# JTAG.net
KiCad netlist of a schematic drawn in Altium Designer
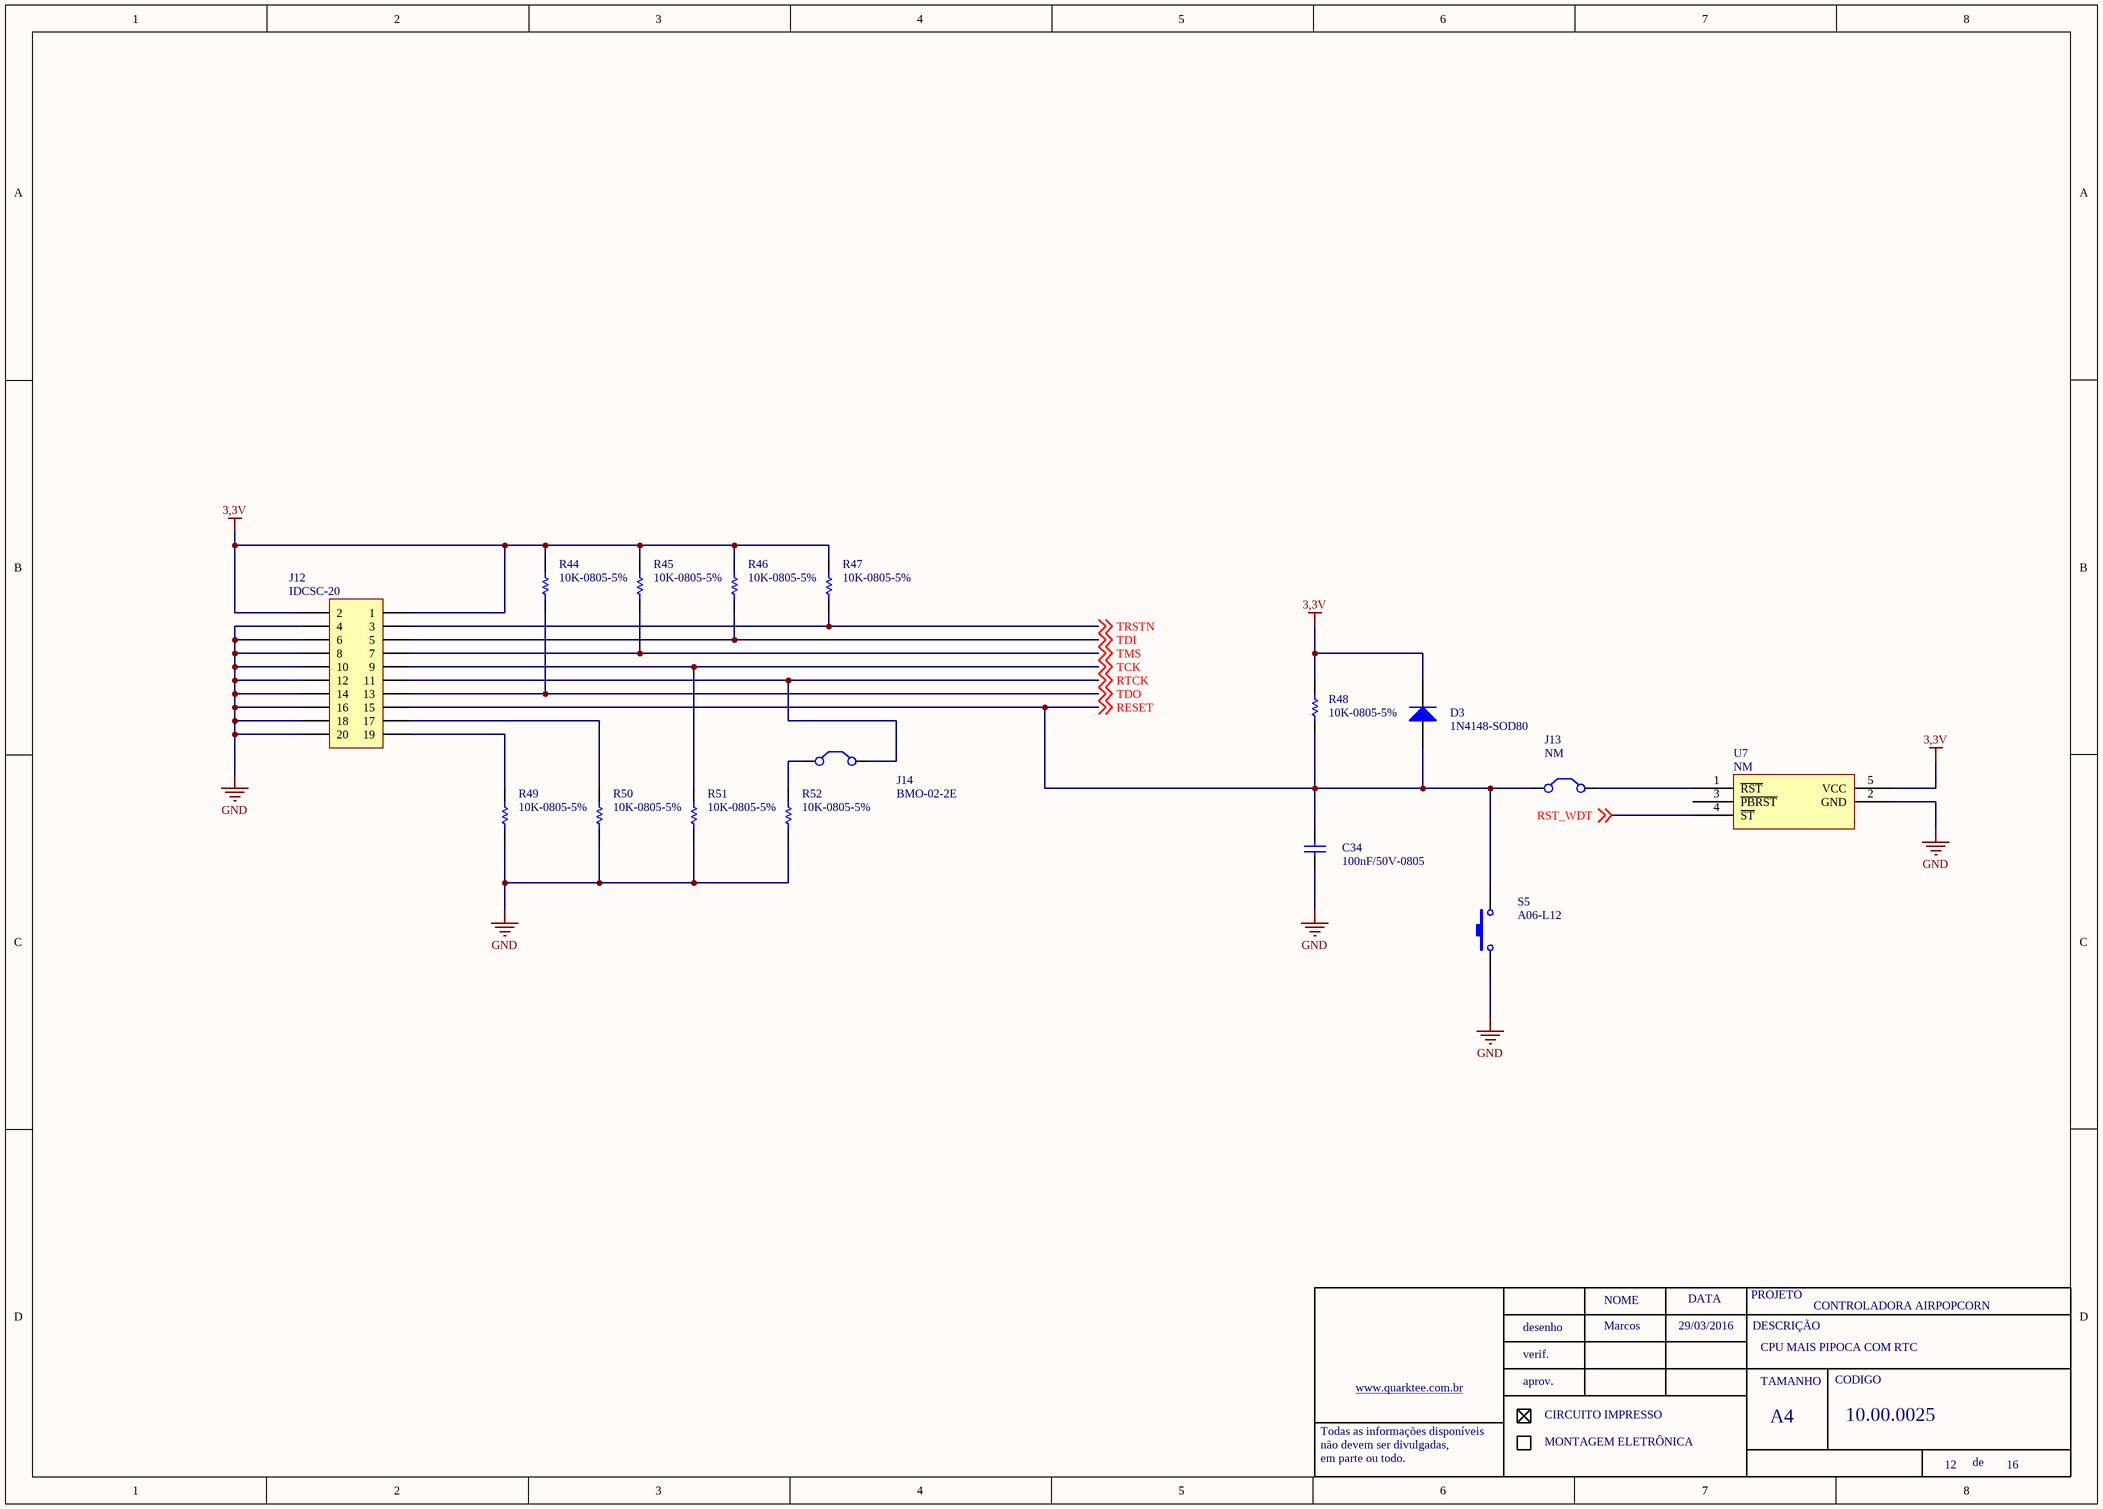
[diagram p0: JTAG.SchDoc]

(export (version "E")
  (design (tool "Eeschema 10.0.6"))
  (components
    (comp (ref "C34")
      (value "100nF/50V-0805")
      (footprint "0805-REVISADO O")
      (description "100nF/50-0805-NPO")
      (libsource (lib "AquinoLib") (part "100nF/50-0805-NPO"))
    )
    (comp (ref "D3")
      (value "1N4148-SOD80")
      (footprint "MINIMLEF/SOD80")
      (libsource (lib "AquinoLib") (part "1N4148-SOD80"))
    )
    (comp (ref "J12")
      (value "IDCSC-20")
      (footprint "IDCSC-20")
      (description "BARRA DE PINOS 10x2 VIAS")
      (libsource (lib "ChaveDigital") (part "HEADER 10x2"))
    )
    (comp (ref "J13")
      (value "NM")
      (footprint "JUMPER100")
      (description "BMO-02-2E")
      (libsource (lib "ChaveDigital3") (part "BARRA DE PINOS"))
    )
    (comp (ref "J14")
      (value "BMO-02-2E")
      (footprint "JUMPER100")
      (libsource (lib "ChaveDigital") (part "BARRA DE PINOS"))
    )
    (comp (ref "R44")
      (value "10K-0805-5%")
      (footprint "0805-REVISADO O")
      (description "RES 10K-0805")
      (libsource (lib "ChaveDigital") (part "RES 10K-0805"))
    )
    (comp (ref "R45")
      (value "10K-0805-5%")
      (footprint "0805-REVISADO O")
      (description "RES 10K-0805")
      (libsource (lib "ChaveDigital") (part "RES 10K-0805"))
    )
    (comp (ref "R46")
      (value "10K-0805-5%")
      (footprint "0805-REVISADO O")
      (description "RES 10K-0805")
      (libsource (lib "ChaveDigital") (part "RES 10K-0805"))
    )
    (comp (ref "R47")
      (value "10K-0805-5%")
      (footprint "0805-REVISADO O")
      (description "RES 10K-0805")
      (libsource (lib "ChaveDigital") (part "RES 10K-0805"))
    )
    (comp (ref "R48")
      (value "10K-0805-5%")
      (footprint "0805-REVISADO O")
      (libsource (lib "AquinoLib") (part "10K-0805-5%"))
    )
    (comp (ref "R49")
      (value "10K-0805-5%")
      (footprint "0805-REVISADO O")
      (description "RES 10K-0805")
      (libsource (lib "ChaveDigital") (part "RES 10K-0805"))
    )
    (comp (ref "R50")
      (value "10K-0805-5%")
      (footprint "0805-REVISADO O")
      (description "RES 10K-0805")
      (libsource (lib "ChaveDigital") (part "RES 10K-0805"))
    )
    (comp (ref "R51")
      (value "10K-0805-5%")
      (footprint "0805-REVISADO O")
      (description "RES 10K-0805")
      (libsource (lib "ChaveDigital") (part "RES 10K-0805"))
    )
    (comp (ref "R52")
      (value "10K-0805-5%")
      (footprint "0805-REVISADO O")
      (description "RES 10K-0805")
      (libsource (lib "ChaveDigital") (part "RES 10K-0805"))
    )
    (comp (ref "S5")
      (value "A06-L12")
      (footprint "CHAVE TACTIL NO_[125](Primary)")
      (libsource (lib "ChaveDigital3") (part "A06-L12"))
    )
    (comp (ref "U7")
      (value "NM")
      (footprint "SOT23-5")
      (description "DS1819A")
      (libsource (lib "ChaveDigital3") (part "DS1819A"))
    )
  )
  (nets
    (net (code "1") (name "3,3V") (class "Default")
      (node (ref "D3") (pin "2") (pinfunction "2_2") (pintype "passive"))
      (node (ref "J12") (pin "1") (pinfunction "1_1") (pintype "passive"))
      (node (ref "J12") (pin "2") (pinfunction "2_2") (pintype "passive"))
      (node (ref "R44") (pin "1") (pinfunction "1_1") (pintype "passive"))
      (node (ref "R45") (pin "1") (pinfunction "1_1") (pintype "passive"))
      (node (ref "R46") (pin "1") (pinfunction "1_1") (pintype "passive"))
      (node (ref "R47") (pin "1") (pinfunction "1_1") (pintype "passive"))
      (node (ref "R48") (pin "2") (pinfunction "2_2") (pintype "passive"))
      (node (ref "U7") (pin "5") (pinfunction "VCC_5") (pintype "passive"))
    )
    (net (code "2") (name "GND") (class "Default")
      (node (ref "C34") (pin "1") (pinfunction "1_1") (pintype "passive"))
      (node (ref "J12") (pin "10") (pinfunction "10_10") (pintype "passive"))
      (node (ref "J12") (pin "12") (pinfunction "12_12") (pintype "passive"))
      (node (ref "J12") (pin "14") (pinfunction "14_14") (pintype "passive"))
      (node (ref "J12") (pin "16") (pinfunction "16_16") (pintype "passive"))
      (node (ref "J12") (pin "18") (pinfunction "18_18") (pintype "passive"))
      (node (ref "J12") (pin "20") (pinfunction "20_20") (pintype "passive"))
      (node (ref "J12") (pin "4") (pinfunction "4_4") (pintype "passive"))
      (node (ref "J12") (pin "6") (pinfunction "6_6") (pintype "passive"))
      (node (ref "J12") (pin "8") (pinfunction "8_8") (pintype "passive"))
      (node (ref "R49") (pin "2") (pinfunction "2_2") (pintype "passive"))
      (node (ref "R50") (pin "2") (pinfunction "2_2") (pintype "passive"))
      (node (ref "R51") (pin "2") (pinfunction "2_2") (pintype "passive"))
      (node (ref "R52") (pin "2") (pinfunction "2_2") (pintype "passive"))
      (node (ref "S5") (pin "1") (pinfunction "1_1") (pintype "passive"))
      (node (ref "U7") (pin "2") (pinfunction "GND_2") (pintype "passive"))
    )
    (net (code "3") (name "Net-(J12-Pad17)") (class "Default")
      (node (ref "J12") (pin "17") (pinfunction "17_17") (pintype "passive"))
      (node (ref "R50") (pin "1") (pinfunction "1_1") (pintype "passive"))
    )
    (net (code "4") (name "Net-(J12-Pad19)") (class "Default")
      (node (ref "J12") (pin "19") (pinfunction "19_19") (pintype "passive"))
      (node (ref "R49") (pin "1") (pinfunction "1_1") (pintype "passive"))
    )
    (net (code "5") (name "Net-(J13-C2)") (class "Default")
      (node (ref "J13") (pin "2") (pinfunction "C2_2") (pintype "passive"))
      (node (ref "U7") (pin "1") (pinfunction "~{RST}_1") (pintype "passive"))
    )
    (net (code "6") (name "Net-(J14-C1)") (class "Default")
      (node (ref "J14") (pin "1") (pinfunction "C1_1") (pintype "passive"))
      (node (ref "R52") (pin "1") (pinfunction "1_1") (pintype "passive"))
    )
    (net (code "7") (name "RESET") (class "Default")
      (node (ref "C34") (pin "2") (pinfunction "2_2") (pintype "passive"))
      (node (ref "D3") (pin "1") (pinfunction "1_1") (pintype "passive"))
      (node (ref "J12") (pin "15") (pinfunction "15_15") (pintype "passive"))
      (node (ref "J13") (pin "1") (pinfunction "C1_1") (pintype "passive"))
      (node (ref "R48") (pin "1") (pinfunction "1_1") (pintype "passive"))
      (node (ref "S5") (pin "2") (pinfunction "2_2") (pintype "passive"))
    )
    (net (code "8") (name "RST_WDT") (class "Default")
      (node (ref "U7") (pin "4") (pinfunction "~{ST}_4") (pintype "passive"))
    )
    (net (code "9") (name "RTCK") (class "Default")
      (node (ref "J12") (pin "11") (pinfunction "11_11") (pintype "passive"))
      (node (ref "J14") (pin "2") (pinfunction "C2_2") (pintype "passive"))
    )
    (net (code "10") (name "TCK") (class "Default")
      (node (ref "J12") (pin "9") (pinfunction "9_9") (pintype "passive"))
      (node (ref "R51") (pin "1") (pinfunction "1_1") (pintype "passive"))
    )
    (net (code "11") (name "TDI") (class "Default")
      (node (ref "J12") (pin "5") (pinfunction "5_5") (pintype "passive"))
      (node (ref "R46") (pin "2") (pinfunction "2_2") (pintype "passive"))
    )
    (net (code "12") (name "TDO") (class "Default")
      (node (ref "J12") (pin "13") (pinfunction "13_13") (pintype "passive"))
      (node (ref "R44") (pin "2") (pinfunction "2_2") (pintype "passive"))
    )
    (net (code "13") (name "TMS") (class "Default")
      (node (ref "J12") (pin "7") (pinfunction "7_7") (pintype "passive"))
      (node (ref "R45") (pin "2") (pinfunction "2_2") (pintype "passive"))
    )
    (net (code "14") (name "TRSTN") (class "Default")
      (node (ref "J12") (pin "3") (pinfunction "3_3") (pintype "passive"))
      (node (ref "R47") (pin "2") (pinfunction "2_2") (pintype "passive"))
    )
    (net (code "15") (name "unconnected-(U7-~{PBRST}-Pad3)") (class "Default")
      (node (ref "U7") (pin "3") (pinfunction "~{PBRST}_3") (pintype "passive"))
    )
  )
)
